# PIC.net
KiCad netlist of a schematic drawn in Altium Designer
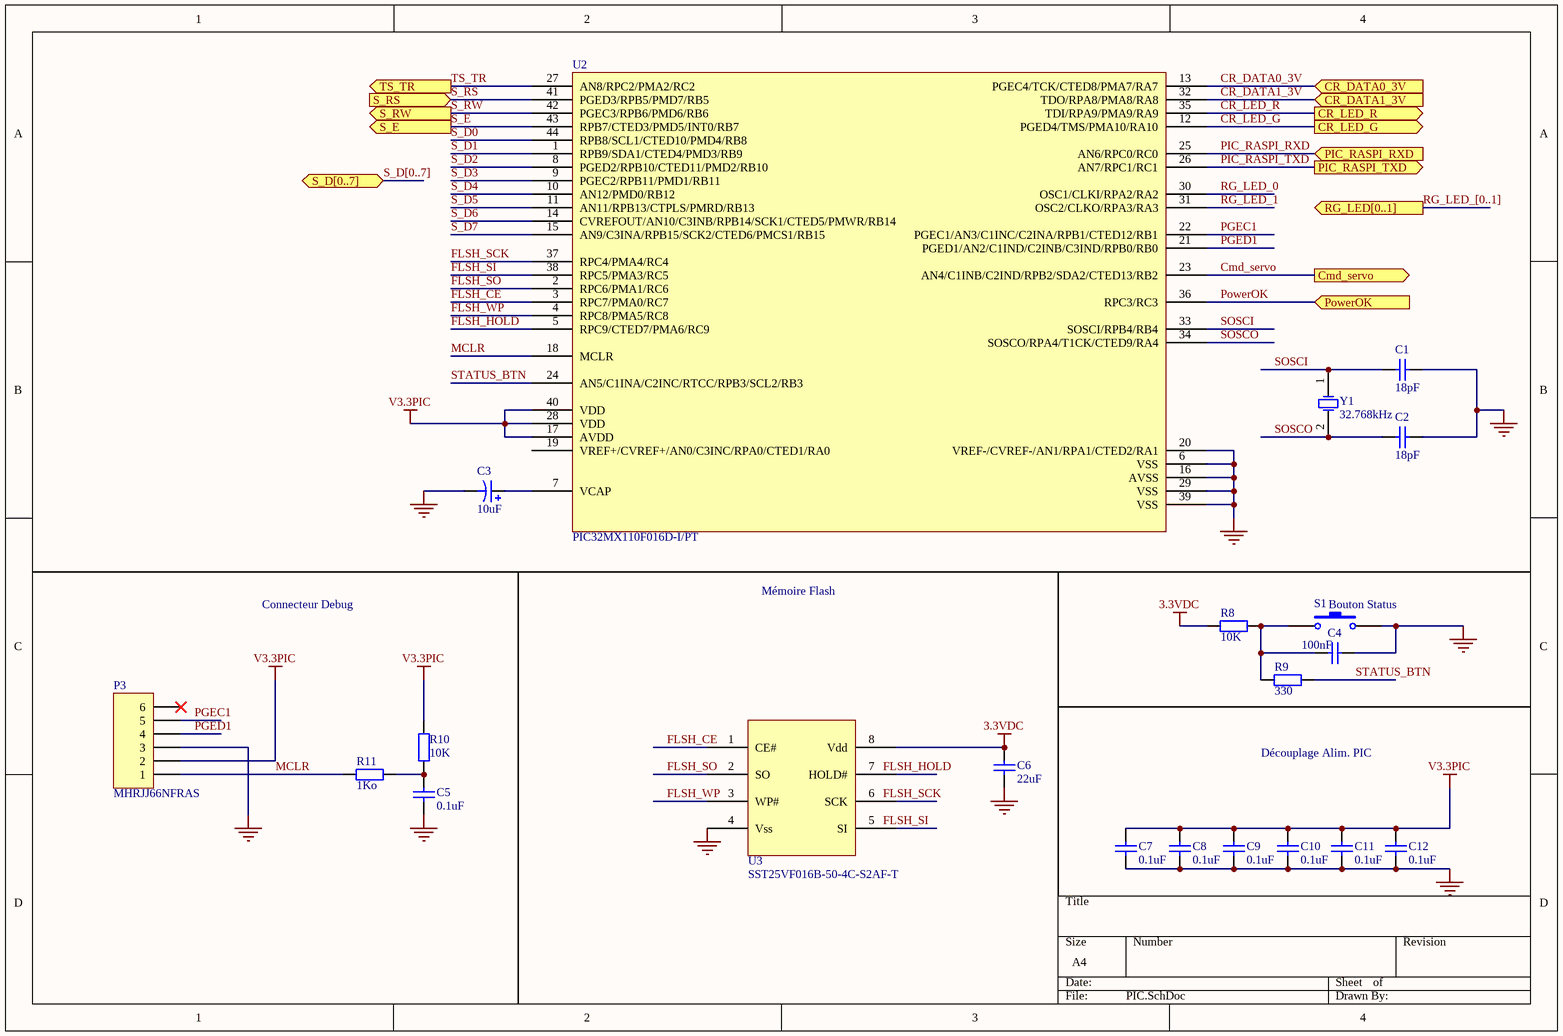
[diagram p0: PIC.SchDoc]

(export (version "E")
  (design (tool "Eeschema 10.0.6"))
  (components
    (comp (ref "C1")
      (value "18pF")
      (footprint "RAD-0.3")
      (description "Capacitor")
      (libsource (lib "Miscellaneous Devices") (part "Cap"))
    )
    (comp (ref "C2")
      (value "18pF")
      (footprint "RAD-0.3")
      (description "Capacitor")
      (libsource (lib "Miscellaneous Devices") (part "Cap"))
    )
    (comp (ref "C3")
      (value "10uF")
      (footprint "RB7.6-15")
      (libsource (lib "Miscellaneous Devices") (part "Cap Pol1"))
    )
    (comp (ref "C4")
      (value "100nF")
      (footprint "RAD-0.3")
      (description "Capacitor")
      (libsource (lib "Miscellaneous Devices") (part "Cap"))
    )
    (comp (ref "C5")
      (value "0.1uF")
      (footprint "RAD-0.3")
      (description "Capacitor")
      (libsource (lib "Miscellaneous Devices") (part "Cap"))
    )
    (comp (ref "C6")
      (value "22uF")
      (footprint "RAD-0.3")
      (description "Cout_Reg_3.3v")
      (libsource (lib "Miscellaneous Devices") (part "Cap"))
    )
    (comp (ref "C7")
      (value "0.1uF")
      (footprint "RAD-0.3")
      (description "Capacitor")
      (libsource (lib "Miscellaneous Devices") (part "Cap"))
    )
    (comp (ref "C8")
      (value "0.1uF")
      (footprint "RAD-0.3")
      (description "Capacitor")
      (libsource (lib "Miscellaneous Devices") (part "Cap"))
    )
    (comp (ref "C9")
      (value "0.1uF")
      (footprint "RAD-0.3")
      (description "Capacitor")
      (libsource (lib "Miscellaneous Devices") (part "Cap"))
    )
    (comp (ref "C10")
      (value "0.1uF")
      (footprint "RAD-0.3")
      (description "Capacitor")
      (libsource (lib "Miscellaneous Devices") (part "Cap"))
    )
    (comp (ref "C11")
      (value "0.1uF")
      (footprint "RAD-0.3")
      (description "Capacitor")
      (libsource (lib "Miscellaneous Devices") (part "Cap"))
    )
    (comp (ref "C12")
      (value "0.1uF")
      (footprint "RAD-0.3")
      (description "Capacitor")
      (libsource (lib "Miscellaneous Devices") (part "Cap"))
    )
    (comp (ref "P3")
      (value "MHRJJ66NFRAS")
      (footprint "HDR1X6")
      (description "PortRJ12_debug")
      (libsource (lib "Miscellaneous Connectors") (part "Header 6"))
    )
    (comp (ref "R8")
      (value "10K")
      (footprint "AXIAL-0.4")
      (description "Resistor")
      (libsource (lib "Miscellaneous Devices") (part "Res2"))
    )
    (comp (ref "R9")
      (value "330")
      (footprint "AXIAL-0.4")
      (description "Resistor")
      (libsource (lib "Miscellaneous Devices") (part "Res2"))
    )
    (comp (ref "R10")
      (value "10K")
      (footprint "AXIAL-0.4")
      (description "Resistor")
      (libsource (lib "") (part "Res2_2"))
    )
    (comp (ref "R11")
      (value "1Ko")
      (footprint "AXIAL-0.4")
      (description "Resistor")
      (libsource (lib "") (part "Res2_1"))
    )
    (comp (ref "S1")
      (value "Bouton Status")
      (footprint "SPST-2")
      (description "Switch")
      (libsource (lib "Miscellaneous Devices") (part "SW-PB"))
    )
    (comp (ref "U2") (value "PIC32MX110F016D-I/PT") (libsource (lib "Schlib1") (part "PIC32")))
    (comp (ref "U3")
      (value "SST25VF016B-50-4C-S2AF-T")
      (description "FLASH")
      (libsource (lib "Schlib1") (part "Memoire"))
    )
    (comp (ref "Y1")
      (value "32.768kHz")
      (footprint "R38")
      (description "Crystal Oscillator")
      (libsource (lib "Miscellaneous Devices") (part "XTAL"))
    )
  )
  (nets
    (net (code "1") (name "/CR_DATA0_3V") (class "Default")
      (node (ref "U2") (pin "13") (pinfunction "PGEC4/TCK/CTED8/PMA7/RA7_13") (pintype "passive"))
    )
    (net (code "2") (name "/CR_DATA1_3V") (class "Default")
      (node (ref "U2") (pin "32") (pinfunction "TDO/RPA8/PMA8/RA8_32") (pintype "passive"))
    )
    (net (code "3") (name "/CR_LED_G") (class "Default")
      (node (ref "U2") (pin "12") (pinfunction "PGED4/TMS/PMA10/RA10_12") (pintype "passive"))
    )
    (net (code "4") (name "/CR_LED_R") (class "Default")
      (node (ref "U2") (pin "35") (pinfunction "TDI/RPA9/PMA9/RA9_35") (pintype "passive"))
    )
    (net (code "5") (name "/Cmd_servo") (class "Default")
      (node (ref "U2") (pin "23") (pinfunction "AN4/C1INB/C2IND/RPB2/SDA2/CTED13/RB2_23") (pintype "passive"))
    )
    (net (code "6") (name "/FLSH_CE") (class "Default")
      (node (ref "U2") (pin "3") (pinfunction "RPC7/PMA0/RC7_3") (pintype "passive"))
      (node (ref "U3") (pin "1") (pinfunction "CE#_1") (pintype "passive"))
    )
    (net (code "7") (name "/FLSH_HOLD") (class "Default")
      (node (ref "U2") (pin "5") (pinfunction "RPC9/CTED7/PMA6/RC9_5") (pintype "passive"))
    )
    (net (code "8") (name "/FLSH_SCK") (class "Default")
      (node (ref "U2") (pin "37") (pinfunction "RPC4/PMA4/RC4_37") (pintype "passive"))
    )
    (net (code "9") (name "/FLSH_SI") (class "Default")
      (node (ref "U2") (pin "38") (pinfunction "RPC5/PMA3/RC5_38") (pintype "passive"))
    )
    (net (code "10") (name "/FLSH_SO") (class "Default")
      (node (ref "U2") (pin "2") (pinfunction "RPC6/PMA1/RC6_2") (pintype "passive"))
      (node (ref "U3") (pin "2") (pinfunction "SO_2") (pintype "passive"))
    )
    (net (code "11") (name "/FLSH_WP") (class "Default")
      (node (ref "U2") (pin "4") (pinfunction "RPC8/PMA5/RC8_4") (pintype "passive"))
      (node (ref "U3") (pin "3") (pinfunction "WP#_3") (pintype "passive"))
    )
    (net (code "12") (name "/MCLR") (class "Default")
      (node (ref "P3") (pin "1") (pinfunction "1_1") (pintype "passive"))
      (node (ref "R11") (pin "2") (pinfunction "2_2") (pintype "passive"))
      (node (ref "U2") (pin "18") (pinfunction "MCLR_18") (pintype "passive"))
    )
    (net (code "13") (name "/PGEC1") (class "Default")
      (node (ref "P3") (pin "5") (pinfunction "5_5") (pintype "passive"))
      (node (ref "U2") (pin "22") (pinfunction "PGEC1/AN3/C1INC/C2INA/RPB1/CTED12/RB1_22") (pintype "passive"))
    )
    (net (code "14") (name "/PGED1") (class "Default")
      (node (ref "P3") (pin "4") (pinfunction "4_4") (pintype "passive"))
      (node (ref "U2") (pin "21") (pinfunction "PGED1/AN2/C1IND/C2INB/C3IND/RPB0/RB0_21") (pintype "passive"))
    )
    (net (code "15") (name "/PIC_RASPI_RXD") (class "Default")
      (node (ref "U2") (pin "25") (pinfunction "AN6/RPC0/RC0_25") (pintype "passive"))
    )
    (net (code "16") (name "/PIC_RASPI_TXD") (class "Default")
      (node (ref "U2") (pin "26") (pinfunction "AN7/RPC1/RC1_26") (pintype "passive"))
    )
    (net (code "17") (name "/PowerOK") (class "Default")
      (node (ref "U2") (pin "36") (pinfunction "RPC3/RC3_36") (pintype "passive"))
    )
    (net (code "18") (name "/RG_LED_0") (class "Default")
      (node (ref "U2") (pin "30") (pinfunction "OSC1/CLKI/RPA2/RA2_30") (pintype "passive"))
    )
    (net (code "19") (name "/RG_LED_1") (class "Default")
      (node (ref "U2") (pin "31") (pinfunction "OSC2/CLKO/RPA3/RA3_31") (pintype "passive"))
    )
    (net (code "21") (name "/SOSCI") (class "Default")
      (node (ref "C1") (pin "2") (pinfunction "2_2") (pintype "passive"))
      (node (ref "U2") (pin "33") (pinfunction "SOSCI/RPB4/RB4_33") (pintype "passive"))
      (node (ref "Y1") (pin "1") (pinfunction "OSC1_1") (pintype "passive"))
    )
    (net (code "22") (name "/SOSCO") (class "Default")
      (node (ref "C2") (pin "2") (pinfunction "2_2") (pintype "passive"))
      (node (ref "U2") (pin "34") (pinfunction "SOSCO/RPA4/T1CK/CTED9/RA4_34") (pintype "passive"))
      (node (ref "Y1") (pin "2") (pinfunction "OSC2_2") (pintype "passive"))
    )
    (net (code "23") (name "/STATUS_BTN") (class "Default")
      (node (ref "R9") (pin "2") (pinfunction "2_2") (pintype "passive"))
      (node (ref "U2") (pin "24") (pinfunction "AN5/C1INA/C2INC/RTCC/RPB3/SCL2/RB3_24") (pintype "passive"))
    )
    (net (code "24") (name "/S_D0") (class "Default")
      (node (ref "U2") (pin "44") (pinfunction "RPB8/SCL1/CTED10/PMD4/RB8_44") (pintype "passive"))
    )
    (net (code "25") (name "/S_D1") (class "Default")
      (node (ref "U2") (pin "1") (pinfunction "RPB9/SDA1/CTED4/PMD3/RB9_1") (pintype "passive"))
    )
    (net (code "26") (name "/S_D2") (class "Default")
      (node (ref "U2") (pin "8") (pinfunction "PGED2/RPB10/CTED11/PMD2/RB10_8") (pintype "passive"))
    )
    (net (code "27") (name "/S_D3") (class "Default")
      (node (ref "U2") (pin "9") (pinfunction "PGEC2/RPB11/PMD1/RB11_9") (pintype "passive"))
    )
    (net (code "28") (name "/S_D4") (class "Default")
      (node (ref "U2") (pin "10") (pinfunction "AN12/PMD0/RB12_10") (pintype "passive"))
    )
    (net (code "29") (name "/S_D5") (class "Default")
      (node (ref "U2") (pin "11") (pinfunction "AN11/RPB13/CTPLS/PMRD/RB13_11") (pintype "passive"))
    )
    (net (code "30") (name "/S_D6") (class "Default")
      (node (ref "U2") (pin "14") (pinfunction "CVREFOUT/AN10/C3INB/RPB14/SCK1/CTED5/PMWR/RB14_14") (pintype "passive"))
    )
    (net (code "31") (name "/S_D7") (class "Default")
      (node (ref "U2") (pin "15") (pinfunction "AN9/C3INA/RPB15/SCK2/CTED6/PMCS1/RB15_15") (pintype "passive"))
    )
    (net (code "33") (name "/S_E") (class "Default")
      (node (ref "U2") (pin "43") (pinfunction "RPB7/CTED3/PMD5/INT0/RB7_43") (pintype "passive"))
    )
    (net (code "34") (name "/S_RS") (class "Default")
      (node (ref "U2") (pin "41") (pinfunction "PGED3/RPB5/PMD7/RB5_41") (pintype "passive"))
    )
    (net (code "35") (name "/S_RW") (class "Default")
      (node (ref "U2") (pin "42") (pinfunction "PGEC3/RPB6/PMD6/RB6_42") (pintype "passive"))
    )
    (net (code "36") (name "/TS_TR") (class "Default")
      (node (ref "U2") (pin "27") (pinfunction "AN8/RPC2/PMA2/RC2_27") (pintype "passive"))
    )
    (net (code "37") (name "3.3VDC") (class "Default")
      (node (ref "C6") (pin "2") (pinfunction "2_2") (pintype "passive"))
      (node (ref "R8") (pin "1") (pinfunction "1_1") (pintype "passive"))
      (node (ref "U3") (pin "8") (pinfunction "Vdd_8") (pintype "passive"))
    )
    (net (code "38") (name "GND") (class "Default")
      (node (ref "C1") (pin "1") (pinfunction "1_1") (pintype "passive"))
      (node (ref "C10") (pin "1") (pinfunction "1_1") (pintype "passive"))
      (node (ref "C11") (pin "1") (pinfunction "1_1") (pintype "passive"))
      (node (ref "C12") (pin "1") (pinfunction "1_1") (pintype "passive"))
      (node (ref "C2") (pin "1") (pinfunction "1_1") (pintype "passive"))
      (node (ref "C3") (pin "2") (pinfunction "2_2") (pintype "passive"))
      (node (ref "C4") (pin "2") (pinfunction "2_2") (pintype "passive"))
      (node (ref "C5") (pin "1") (pinfunction "1_1") (pintype "passive"))
      (node (ref "C6") (pin "1") (pinfunction "1_1") (pintype "passive"))
      (node (ref "C7") (pin "1") (pinfunction "1_1") (pintype "passive"))
      (node (ref "C8") (pin "1") (pinfunction "1_1") (pintype "passive"))
      (node (ref "C9") (pin "1") (pinfunction "1_1") (pintype "passive"))
      (node (ref "P3") (pin "3") (pinfunction "3_3") (pintype "passive"))
      (node (ref "S1") (pin "2") (pinfunction "2_2") (pintype "passive"))
      (node (ref "U2") (pin "16") (pinfunction "AVSS_16") (pintype "passive"))
      (node (ref "U2") (pin "20") (pinfunction "VREF-/CVREF-/AN1/RPA1/CTED2/RA1_20") (pintype "passive"))
      (node (ref "U2") (pin "29") (pinfunction "VSS_29") (pintype "passive"))
      (node (ref "U2") (pin "39") (pinfunction "VSS_39") (pintype "passive"))
      (node (ref "U2") (pin "6") (pinfunction "VSS_6") (pintype "passive"))
      (node (ref "U3") (pin "4") (pinfunction "Vss_4") (pintype "passive"))
    )
    (net (code "39") (name "Net-(C4-Pad1)") (class "Default")
      (node (ref "C4") (pin "1") (pinfunction "1_1") (pintype "passive"))
      (node (ref "R8") (pin "2") (pinfunction "2_2") (pintype "passive"))
      (node (ref "R9") (pin "1") (pinfunction "1_1") (pintype "passive"))
      (node (ref "S1") (pin "1") (pinfunction "1_1") (pintype "passive"))
    )
    (net (code "40") (name "Net-(C5-Pad2)") (class "Default")
      (node (ref "C5") (pin "2") (pinfunction "2_2") (pintype "passive"))
      (node (ref "R10") (pin "1") (pinfunction "1_1") (pintype "passive"))
      (node (ref "R11") (pin "1") (pinfunction "1_1") (pintype "passive"))
    )
    (net (code "41") (name "Net-(U2-VCAP)") (class "Default")
      (node (ref "C3") (pin "1") (pinfunction "1_1") (pintype "passive"))
      (node (ref "U2") (pin "7") (pinfunction "VCAP_7") (pintype "passive"))
    )
    (net (code "42") (name "V3.3PIC") (class "Default")
      (node (ref "C10") (pin "2") (pinfunction "2_2") (pintype "passive"))
      (node (ref "C11") (pin "2") (pinfunction "2_2") (pintype "passive"))
      (node (ref "C12") (pin "2") (pinfunction "2_2") (pintype "passive"))
      (node (ref "C7") (pin "2") (pinfunction "2_2") (pintype "passive"))
      (node (ref "C8") (pin "2") (pinfunction "2_2") (pintype "passive"))
      (node (ref "C9") (pin "2") (pinfunction "2_2") (pintype "passive"))
      (node (ref "P3") (pin "2") (pinfunction "2_2") (pintype "passive"))
      (node (ref "R10") (pin "2") (pinfunction "2_2") (pintype "passive"))
      (node (ref "U2") (pin "17") (pinfunction "AVDD_17") (pintype "passive"))
      (node (ref "U2") (pin "28") (pinfunction "VDD_28") (pintype "passive"))
      (node (ref "U2") (pin "40") (pinfunction "VDD_40") (pintype "passive"))
    )
    (net (code "43") (name "unconnected-(P3-Pad6)") (class "Default")
      (node (ref "P3") (pin "6") (pinfunction "6_6") (pintype "passive+no_connect"))
    )
    (net (code "44") (name "unconnected-(U2-VREF+{slash}CVREF+{slash}AN0{slash}C3INC{slash}RPA0{slash}CTED1{slash}RA0-Pad19)") (class "Default")
      (node (ref "U2") (pin "19") (pinfunction "VREF+/CVREF+/AN0/C3INC/RPA0/CTED1/RA0_19") (pintype "passive"))
    )
    (net (code "45") (name "unconnected-(U3-HOLD#-Pad7)") (class "Default")
      (node (ref "U3") (pin "7") (pinfunction "HOLD#_7") (pintype "passive"))
    )
    (net (code "46") (name "unconnected-(U3-SCK-Pad6)") (class "Default")
      (node (ref "U3") (pin "6") (pinfunction "SCK_6") (pintype "passive"))
    )
    (net (code "47") (name "unconnected-(U3-SI-Pad5)") (class "Default")
      (node (ref "U3") (pin "5") (pinfunction "SI_5") (pintype "passive"))
    )
  )
)
